# Converter_shematic.net
KiCad netlist of a schematic drawn in Altium Designer
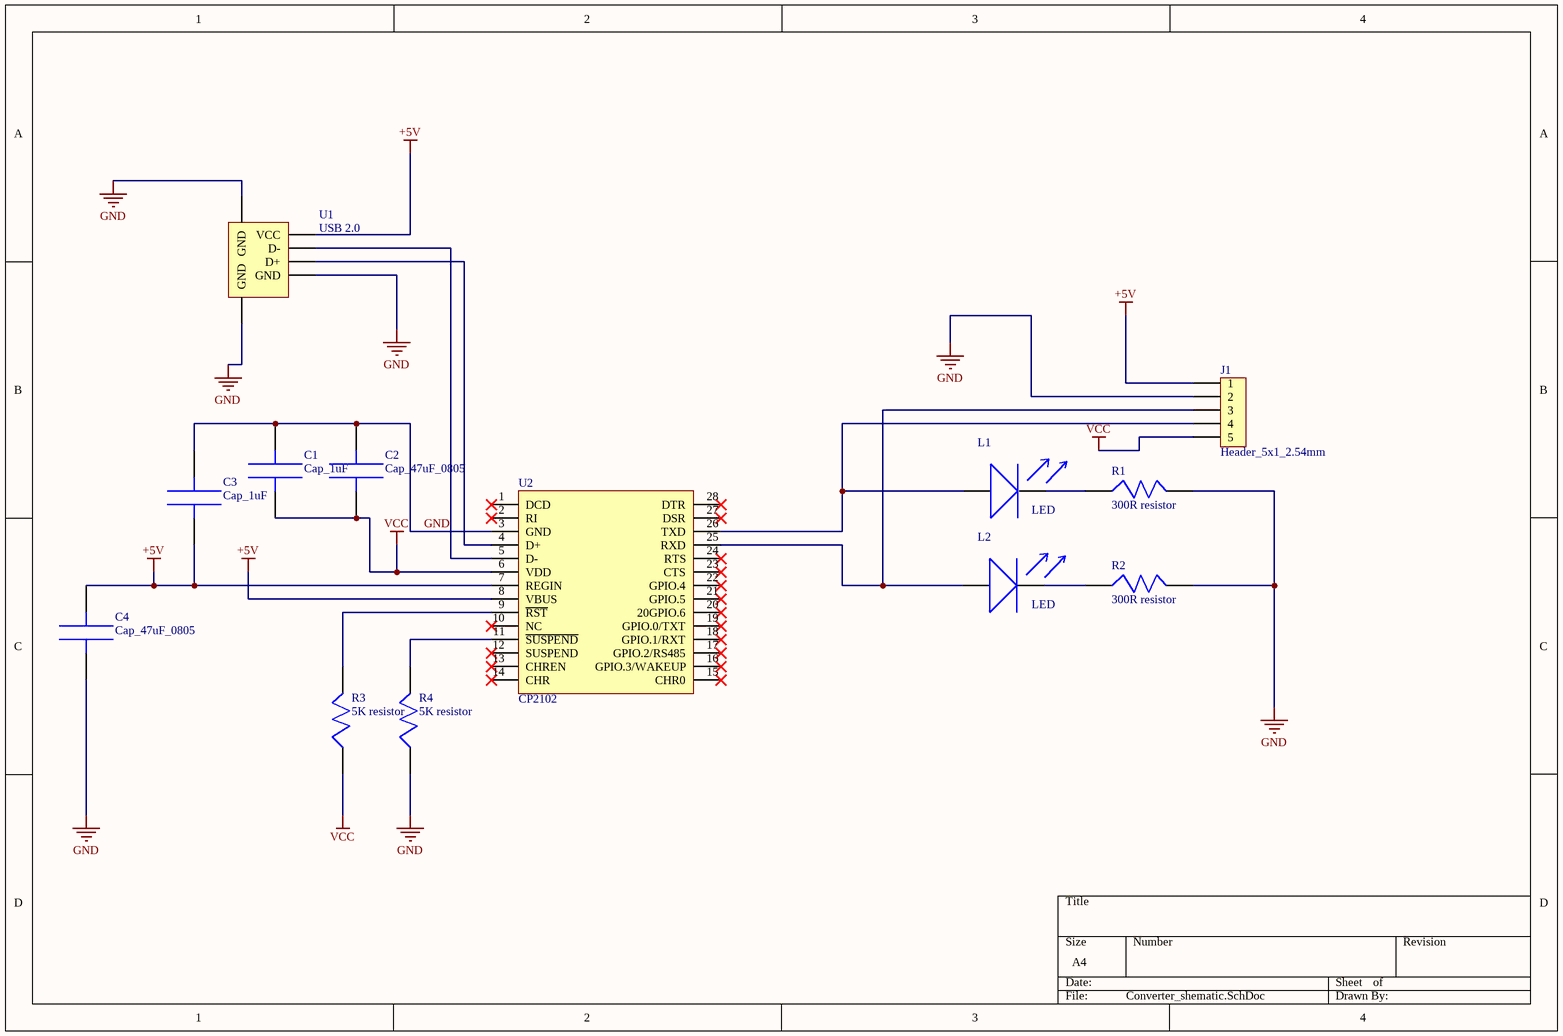
[diagram p0: Converter_shematic.SchDoc]

(export (version "E")
  (design (tool "Eeschema 10.0.6"))
  (components
    (comp (ref "C1")
      (value "Cap_1uF")
      (footprint "Cap_1uF_0805")
      (description "Cap 1uF")
      (libsource (lib "SCH_Library_UART-USB") (part "CAP 1uF"))
    )
    (comp (ref "C2")
      (value "Cap_47uF_0805")
      (footprint "Cap_47uF_0805")
      (fields
        (field (name "MANUFACTURER") "TDK")
        (field (name "MANUFACTURER PART NUMBER") "C2012X5R1A476M125AC")
        (field (name "TOLERANCE") "20%")
      )
      (libsource (lib "SCH_Library_UART-USB") (part "Cap_47uF_0805"))
    )
    (comp (ref "C3")
      (value "Cap_1uF")
      (footprint "Cap_1uF_0805")
      (description "Cap 1uF")
      (libsource (lib "SCH_Library_UART-USB") (part "CAP 1uF"))
    )
    (comp (ref "C4")
      (value "Cap_47uF_0805")
      (footprint "Cap_47uF_0805")
      (fields
        (field (name "MANUFACTURER") "TDK")
        (field (name "MANUFACTURER PART NUMBER") "C2012X5R1A476M125AC")
        (field (name "TOLERANCE") "20%")
      )
      (libsource (lib "SCH_Library_UART-USB") (part "Cap_47uF_0805"))
    )
    (comp (ref "J1")
      (value "Header_5x1_2.54mm")
      (footprint "header_5")
      (fields
        (field (name "MANUFACTURER") "Adam Equipment")
        (field (name "MANUFACTURER PART NUMBER") "PH1RA-05-UA")
      )
      (libsource (lib "SCH_Library_UART-USB") (part "PH1RA-05-UA"))
    )
    (comp (ref "L1")
      (value "LED")
      (footprint "LED")
      (description "LED BLUE CLEAR CHIP SMD")
      (fields
        (field (name "MANUFACTURER") "Vishay Lite-On")
        (field (name "MANUFACTURER PART NUMBER") "LTST-C171TBKT")
      )
      (libsource (lib "SCH_Library_UART-USB") (part "LTST-C171TBKT"))
    )
    (comp (ref "L2")
      (value "LED")
      (footprint "LED")
      (description "LED BLUE CLEAR CHIP SMD")
      (fields
        (field (name "MANUFACTURER") "Vishay Lite-On")
        (field (name "MANUFACTURER PART NUMBER") "LTST-C171TBKT")
      )
      (libsource (lib "SCH_Library_UART-USB") (part "LTST-C171TBKT"))
    )
    (comp (ref "R1")
      (value "300R resistor")
      (footprint "Resistor_0805_300R")
      (description "Res Thick Film 0805 300 Ohm 5% 1/8W 100ppm/C SMD Paper T/R")
      (fields
        (field (name "MANUFACTURER") "Yageo")
        (field (name "MANUFACTURER PART NUMBER") "RC0805JR-07300RL")
      )
      (libsource (lib "SCH_Library_UART-USB") (part "RC0805JR-07300RL"))
    )
    (comp (ref "R2")
      (value "300R resistor")
      (footprint "Resistor_0805_300R")
      (description "Res Thick Film 0805 300 Ohm 5% 1/8W 100ppm/C SMD Paper T/R")
      (fields
        (field (name "MANUFACTURER") "Yageo")
        (field (name "MANUFACTURER PART NUMBER") "RC0805JR-07300RL")
      )
      (libsource (lib "SCH_Library_UART-USB") (part "RC0805JR-07300RL"))
    )
    (comp (ref "R3")
      (value "5K resistor")
      (footprint "Resistor_0805")
      (description "RES SMD 5K OHM 0.05% 1/8W 0805")
      (fields
        (field (name "MANUFACTURER") "Vishay Dale")
        (field (name "MANUFACTURER PART NUMBER") "TNPU08055K00AZEN00")
      )
      (libsource (lib "SCH_Library_UART-USB") (part "Resistor_5K"))
    )
    (comp (ref "R4")
      (value "5K resistor")
      (footprint "Resistor_0805")
      (description "RES SMD 5K OHM 0.05% 1/8W 0805")
      (fields
        (field (name "MANUFACTURER") "Vishay Dale")
        (field (name "MANUFACTURER PART NUMBER") "TNPU08055K00AZEN00")
      )
      (libsource (lib "SCH_Library_UART-USB") (part "Resistor_5K"))
    )
    (comp (ref "U1")
      (value "USB 2.0")
      (footprint "USB")
      (description "CONN PLUG USB A 4POS SMD R/A")
      (fields (field (name "MANUFACTURER") "Molex") (field (name "MANUFACTURER PART NUMBER") "0480372200"))
      (libsource (lib "SCH_Library_UART-USB") (part "USB 2.0"))
    )
    (comp (ref "U2")
      (value "CP2102")
      (footprint "CP2102")
      (description "CP2102 UART-USB converter Module")
      (libsource (lib "SCH_Library_UART-USB") (part "CP2102"))
    )
  )
  (nets
    (net (code "1") (name "+5V") (class "Default")
      (node (ref "C3") (pin "1") (pinfunction "1_1") (pintype "passive"))
      (node (ref "C4") (pin "2") (pinfunction "2_2") (pintype "passive"))
      (node (ref "J1") (pin "1") (pinfunction "1_1") (pintype "passive"))
      (node (ref "U1") (pin "1") (pinfunction "VCC_1") (pintype "passive"))
      (node (ref "U2") (pin "7") (pinfunction "REGIN_7") (pintype "passive"))
      (node (ref "U2") (pin "8") (pinfunction "VBUS_8") (pintype "passive"))
    )
    (net (code "2") (name "GND") (class "Default")
      (node (ref "C1") (pin "2") (pinfunction "2_2") (pintype "passive"))
      (node (ref "C2") (pin "2") (pinfunction "2_2") (pintype "passive"))
      (node (ref "C3") (pin "2") (pinfunction "2_2") (pintype "passive"))
      (node (ref "C4") (pin "1") (pinfunction "1_1") (pintype "passive"))
      (node (ref "J1") (pin "2") (pinfunction "2_2") (pintype "passive"))
      (node (ref "R1") (pin "2") (pinfunction "2_2") (pintype "passive"))
      (node (ref "R2") (pin "2") (pinfunction "2_2") (pintype "passive"))
      (node (ref "R4") (pin "1") (pinfunction "1_1") (pintype "passive"))
      (node (ref "U1") (pin "4") (pinfunction "GND_4") (pintype "passive"))
      (node (ref "U1") (pin "5") (pinfunction "GND_5") (pintype "passive"))
      (node (ref "U1") (pin "6") (pinfunction "GND_6") (pintype "passive"))
      (node (ref "U2") (pin "3") (pinfunction "GND_3") (pintype "passive"))
    )
    (net (code "3") (name "Net-(L1-Anode)") (class "Default")
      (node (ref "J1") (pin "4") (pinfunction "4_4") (pintype "passive"))
      (node (ref "L1") (pin "1") (pinfunction "Anode_1") (pintype "passive"))
      (node (ref "U2") (pin "26") (pinfunction "TXD_26") (pintype "passive"))
    )
    (net (code "4") (name "Net-(L1-Cathode)") (class "Default")
      (node (ref "L1") (pin "2") (pinfunction "Cathode_2") (pintype "passive"))
      (node (ref "R1") (pin "1") (pinfunction "1_1") (pintype "passive"))
    )
    (net (code "5") (name "Net-(L2-Anode)") (class "Default")
      (node (ref "J1") (pin "3") (pinfunction "3_3") (pintype "passive"))
      (node (ref "L2") (pin "1") (pinfunction "Anode_1") (pintype "passive"))
      (node (ref "U2") (pin "25") (pinfunction "RXD_25") (pintype "passive"))
    )
    (net (code "6") (name "Net-(L2-Cathode)") (class "Default")
      (node (ref "L2") (pin "2") (pinfunction "Cathode_2") (pintype "passive"))
      (node (ref "R2") (pin "1") (pinfunction "1_1") (pintype "passive"))
    )
    (net (code "7") (name "Net-(U1-D+)") (class "Default")
      (node (ref "U1") (pin "3") (pinfunction "D+_3") (pintype "passive"))
      (node (ref "U2") (pin "4") (pinfunction "D+_4") (pintype "passive"))
    )
    (net (code "8") (name "Net-(U1-D-)") (class "Default")
      (node (ref "U1") (pin "2") (pinfunction "D-_2") (pintype "passive"))
      (node (ref "U2") (pin "5") (pinfunction "D-_5") (pintype "passive"))
    )
    (net (code "9") (name "Net-(U2-~{RST})") (class "Default")
      (node (ref "R3") (pin "2") (pinfunction "2_2") (pintype "passive"))
      (node (ref "U2") (pin "9") (pinfunction "~{RST}_9") (pintype "passive"))
    )
    (net (code "10") (name "Net-(U2-~{SUSPEND})") (class "Default")
      (node (ref "R4") (pin "2") (pinfunction "2_2") (pintype "passive"))
      (node (ref "U2") (pin "11") (pinfunction "~{SUSPEND}_11") (pintype "passive"))
    )
    (net (code "11") (name "VCC") (class "Default")
      (node (ref "C1") (pin "1") (pinfunction "1_1") (pintype "passive"))
      (node (ref "C2") (pin "1") (pinfunction "1_1") (pintype "passive"))
      (node (ref "J1") (pin "5") (pinfunction "5_5") (pintype "passive"))
      (node (ref "R3") (pin "1") (pinfunction "1_1") (pintype "passive"))
      (node (ref "U2") (pin "6") (pinfunction "VDD_6") (pintype "passive"))
    )
    (net (code "12") (name "unconnected-(U2-20GPIO.6-Pad20)") (class "Default")
      (node (ref "U2") (pin "20") (pinfunction "20GPIO.6_20") (pintype "passive+no_connect"))
    )
    (net (code "13") (name "unconnected-(U2-CHR-Pad14)") (class "Default")
      (node (ref "U2") (pin "14") (pinfunction "CHR_14") (pintype "passive+no_connect"))
    )
    (net (code "14") (name "unconnected-(U2-CHR0-Pad15)") (class "Default")
      (node (ref "U2") (pin "15") (pinfunction "CHR0_15") (pintype "passive+no_connect"))
    )
    (net (code "15") (name "unconnected-(U2-CHREN-Pad13)") (class "Default")
      (node (ref "U2") (pin "13") (pinfunction "CHREN_13") (pintype "passive+no_connect"))
    )
    (net (code "16") (name "unconnected-(U2-CTS-Pad23)") (class "Default")
      (node (ref "U2") (pin "23") (pinfunction "CTS_23") (pintype "passive+no_connect"))
    )
    (net (code "17") (name "unconnected-(U2-DCD-Pad1)") (class "Default")
      (node (ref "U2") (pin "1") (pinfunction "DCD_1") (pintype "passive+no_connect"))
    )
    (net (code "18") (name "unconnected-(U2-DSR-Pad27)") (class "Default")
      (node (ref "U2") (pin "27") (pinfunction "DSR_27") (pintype "passive+no_connect"))
    )
    (net (code "19") (name "unconnected-(U2-DTR-Pad28)") (class "Default")
      (node (ref "U2") (pin "28") (pinfunction "DTR_28") (pintype "passive+no_connect"))
    )
    (net (code "20") (name "unconnected-(U2-GPIO.0{slash}TXT-Pad19)") (class "Default")
      (node (ref "U2") (pin "19") (pinfunction "GPIO.0/TXT_19") (pintype "passive+no_connect"))
    )
    (net (code "21") (name "unconnected-(U2-GPIO.1{slash}RXT-Pad18)") (class "Default")
      (node (ref "U2") (pin "18") (pinfunction "GPIO.1/RXT_18") (pintype "passive+no_connect"))
    )
    (net (code "22") (name "unconnected-(U2-GPIO.2{slash}RS485-Pad17)") (class "Default")
      (node (ref "U2") (pin "17") (pinfunction "GPIO.2/RS485_17") (pintype "passive+no_connect"))
    )
    (net (code "23") (name "unconnected-(U2-GPIO.3{slash}WAKEUP-Pad16)") (class "Default")
      (node (ref "U2") (pin "16") (pinfunction "GPIO.3/WAKEUP_16") (pintype "passive+no_connect"))
    )
    (net (code "24") (name "unconnected-(U2-GPIO.4-Pad22)") (class "Default")
      (node (ref "U2") (pin "22") (pinfunction "GPIO.4_22") (pintype "passive+no_connect"))
    )
    (net (code "25") (name "unconnected-(U2-GPIO.5-Pad21)") (class "Default")
      (node (ref "U2") (pin "21") (pinfunction "GPIO.5_21") (pintype "passive+no_connect"))
    )
    (net (code "26") (name "unconnected-(U2-NC-Pad10)") (class "Default")
      (node (ref "U2") (pin "10") (pinfunction "NC_10") (pintype "passive+no_connect"))
    )
    (net (code "27") (name "unconnected-(U2-RI-Pad2)") (class "Default")
      (node (ref "U2") (pin "2") (pinfunction "RI_2") (pintype "passive+no_connect"))
    )
    (net (code "28") (name "unconnected-(U2-RTS-Pad24)") (class "Default")
      (node (ref "U2") (pin "24") (pinfunction "RTS_24") (pintype "passive+no_connect"))
    )
    (net (code "29") (name "unconnected-(U2-SUSPEND-Pad12)") (class "Default")
      (node (ref "U2") (pin "12") (pinfunction "SUSPEND_12") (pintype "passive+no_connect"))
    )
  )
)
